# CodecB.net
KiCad netlist of a schematic drawn in Altium Designer
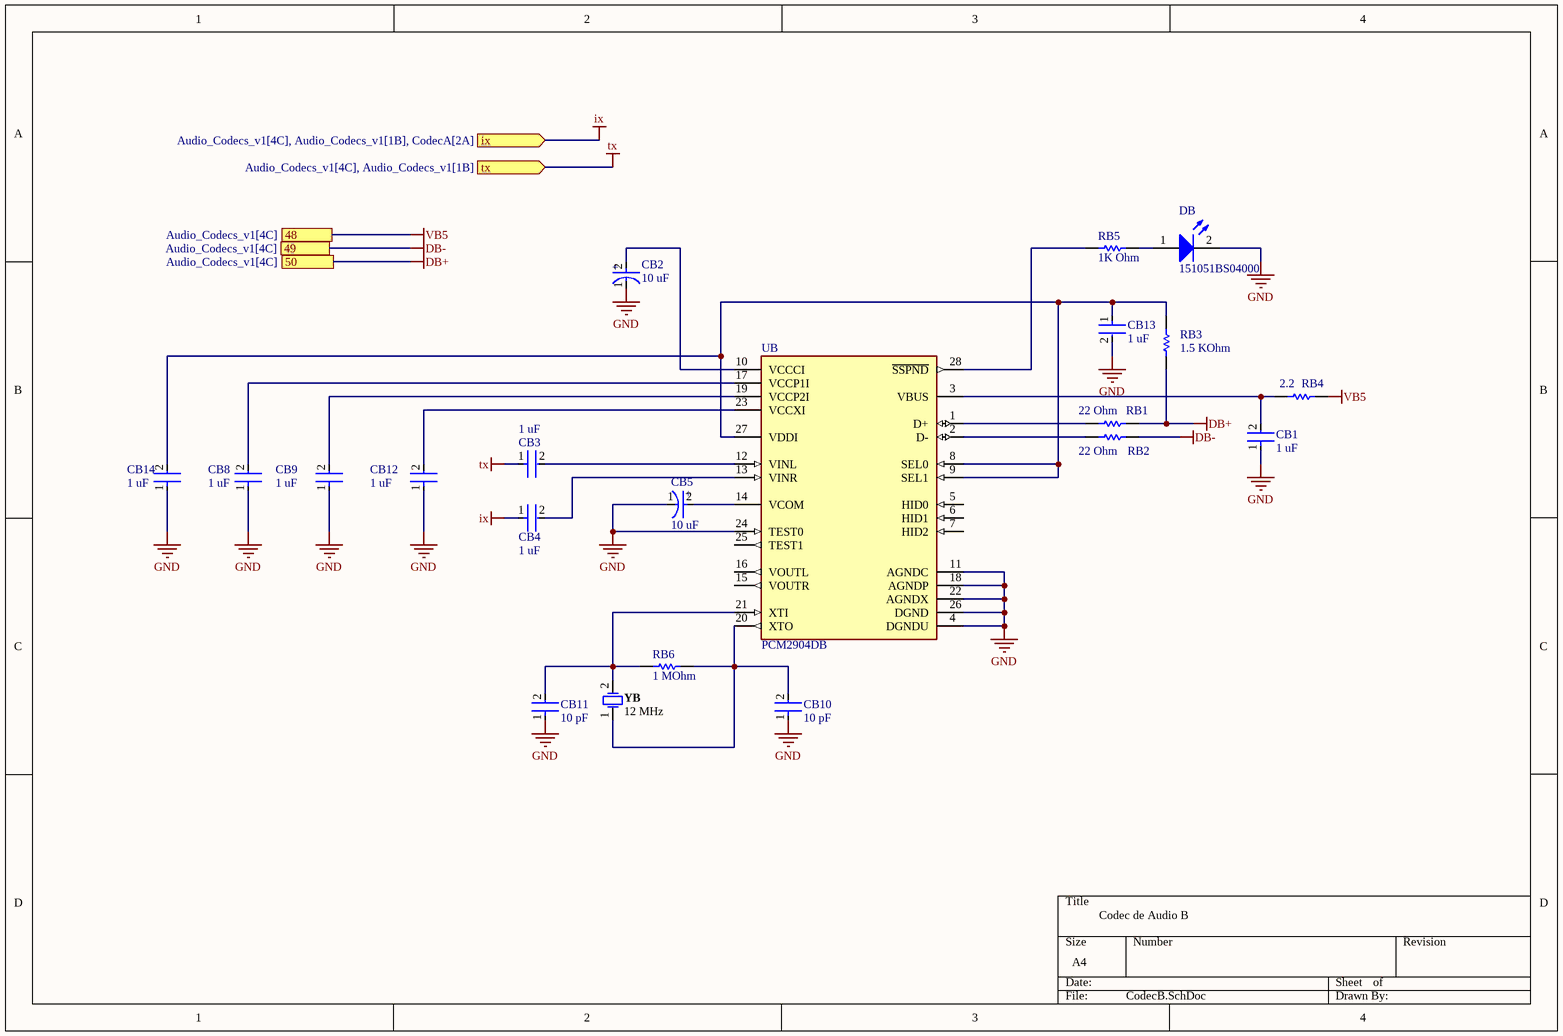
[diagram p0: CodecB.SchDoc]

(export (version "E")
  (design (tool "Eeschema 10.0.6"))
  (components
    (comp (ref "CB1")
      (value "1 uF")
      (footprint "FP-CC0805-0_85-MFG")
      (description "CAP CER 0.1UF 50V X7R 0805")
      (fields (field (name "TOLERANCE") "0.1") (field (name "MANUFACTURER PART NUMBER") "CC0805KRX7R9BB104"))
      (libsource (lib "Altium Content Vault") (part "11868f565c42a9108669ba33697ecf6"))
    )
    (comp (ref "CB2")
      (value "10 uF")
      (footprint "FP-RAD-TH-D_6_3_0_5-L_7_1-MFG")
      (description "Aluminum Electrolytic Capacitors (Radial Lead Type) 100uF ±20% 16V")
      (fields (field (name "VOLTAGE") "16V") (field (name "TOLERANCE") "20%"))
      (libsource (lib "Altium Content Vault") (part "a00bbbee19879c290e62620ae7e47b1"))
    )
    (comp (ref "CB3")
      (value "1 uF")
      (footprint "FP-CC0805-0_85-MFG")
      (description "CAP CER 0.1UF 50V X7R 0805")
      (fields (field (name "TOLERANCE") "0.1") (field (name "MANUFACTURER PART NUMBER") "CC0805KRX7R9BB104"))
      (libsource (lib "Altium Content Vault") (part "11868f565c42a9108669ba33697ecf6"))
    )
    (comp (ref "CB4")
      (value "1 uF")
      (footprint "FP-CC0805-0_85-MFG")
      (description "CAP CER 0.1UF 50V X7R 0805")
      (fields (field (name "TOLERANCE") "0.1") (field (name "MANUFACTURER PART NUMBER") "CC0805KRX7R9BB104"))
      (libsource (lib "Altium Content Vault") (part "11868f565c42a9108669ba33697ecf6"))
    )
    (comp (ref "CB5")
      (value "10 uF")
      (footprint "FP-RAD-TH-D_6_3_0_5-L_7_1-MFG")
      (description "Aluminum Electrolytic Capacitors (Radial Lead Type) 100uF ±20% 16V")
      (fields (field (name "VOLTAGE") "16V") (field (name "TOLERANCE") "20%"))
      (libsource (lib "Altium Content Vault") (part "a00bbbee19879c290e62620ae7e47b1"))
    )
    (comp (ref "CB8")
      (value "1 uF")
      (footprint "FP-CC0805-0_85-MFG")
      (description "CAP CER 0.1UF 50V X7R 0805")
      (fields (field (name "TOLERANCE") "0.1") (field (name "MANUFACTURER PART NUMBER") "CC0805KRX7R9BB104"))
      (libsource (lib "Altium Content Vault") (part "11868f565c42a9108669ba33697ecf6"))
    )
    (comp (ref "CB9")
      (value "1 uF")
      (footprint "FP-CC0805-0_85-MFG")
      (description "CAP CER 0.1UF 50V X7R 0805")
      (fields (field (name "TOLERANCE") "0.1") (field (name "MANUFACTURER PART NUMBER") "CC0805KRX7R9BB104"))
      (libsource (lib "Altium Content Vault") (part "11868f565c42a9108669ba33697ecf6"))
    )
    (comp (ref "CB10")
      (value "10 pF")
      (footprint "FP-CC0805-0_85-MFG")
      (description "CAP CER 0.1UF 50V X7R 0805")
      (fields (field (name "TOLERANCE") "0.1") (field (name "MANUFACTURER PART NUMBER") "CC0805KRX7R9BB104"))
      (libsource (lib "Altium Content Vault") (part "11868f565c42a9108669ba33697ecf6"))
    )
    (comp (ref "CB11")
      (value "10 pF")
      (footprint "FP-CC0805-0_85-MFG")
      (description "CAP CER 0.1UF 50V X7R 0805")
      (fields (field (name "TOLERANCE") "0.1") (field (name "MANUFACTURER PART NUMBER") "CC0805KRX7R9BB104"))
      (libsource (lib "Altium Content Vault") (part "11868f565c42a9108669ba33697ecf6"))
    )
    (comp (ref "CB12")
      (value "1 uF")
      (footprint "FP-CC0805-0_85-MFG")
      (description "CAP CER 0.1UF 50V X7R 0805")
      (fields (field (name "TOLERANCE") "0.1") (field (name "MANUFACTURER PART NUMBER") "CC0805KRX7R9BB104"))
      (libsource (lib "Altium Content Vault") (part "11868f565c42a9108669ba33697ecf6"))
    )
    (comp (ref "CB13")
      (value "1 uF")
      (footprint "FP-CC0805-0_85-MFG")
      (description "CAP CER 0.1UF 50V X7R 0805")
      (fields (field (name "TOLERANCE") "0.1") (field (name "MANUFACTURER PART NUMBER") "CC0805KRX7R9BB104"))
      (libsource (lib "Altium Content Vault") (part "11868f565c42a9108669ba33697ecf6"))
    )
    (comp (ref "CB14")
      (value "1 uF")
      (footprint "FP-CC0805-0_85-MFG")
      (description "CAP CER 0.1UF 50V X7R 0805")
      (fields (field (name "TOLERANCE") "0.1") (field (name "MANUFACTURER PART NUMBER") "CC0805KRX7R9BB104"))
      (libsource (lib "Altium Content Vault") (part "11868f565c42a9108669ba33697ecf6"))
    )
    (comp (ref "DB")
      (value "151051BS04000")
      (footprint "WL-TMRC_D5.9H8.7")
      (libsource (lib "Altium Content Vault") (part "LED_Blue_1A-2K"))
    )
    (comp (ref "RB1")
      (value "22 Ohm")
      (footprint "RESC2013X60X40ML20T25")
      (fields (field (name "MANUFACTURER") "Panasonic") (field (name "PART NUMBER") "ERA6AEB101V"))
      (libsource (lib "Altium Content Vault") (part "RES"))
    )
    (comp (ref "RB2")
      (value "22 Ohm")
      (footprint "RESC2013X60X40ML20T25")
      (fields (field (name "MANUFACTURER") "Panasonic") (field (name "PART NUMBER") "ERA6AEB101V"))
      (libsource (lib "Altium Content Vault") (part "RES"))
    )
    (comp (ref "RB3")
      (value "1.5 KOhm")
      (footprint "RESC2013X60X40ML20T25")
      (fields (field (name "MANUFACTURER") "Panasonic") (field (name "PART NUMBER") "ERA6AEB101V"))
      (libsource (lib "Altium Content Vault") (part "RES"))
    )
    (comp (ref "RB4")
      (value "2.2")
      (footprint "RESC2013X60X40ML20T25")
      (fields (field (name "MANUFACTURER") "Panasonic") (field (name "PART NUMBER") "ERA6AEB101V"))
      (libsource (lib "Altium Content Vault") (part "RES"))
    )
    (comp (ref "RB5")
      (value "1K Ohm")
      (footprint "RESC2013X60X40ML20T25")
      (fields (field (name "MANUFACTURER") "Panasonic") (field (name "PART NUMBER") "ERA6AEB101V"))
      (libsource (lib "Altium Content Vault") (part "RES"))
    )
    (comp (ref "RB6")
      (value "1 MOhm")
      (footprint "RESC2013X60X40ML20T25")
      (fields (field (name "MANUFACTURER") "Panasonic") (field (name "PART NUMBER") "ERA6AEB101V"))
      (libsource (lib "Altium Content Vault") (part "RES"))
    )
    (comp (ref "UB")
      (value "PCM2904DB")
      (footprint "FP-DB0028A-IPC_A")
      (description "IC STEREO AUD CODEC W/USB 28SSOP")
      (libsource (lib "Altium Content Vault") (part "e359a79613c207c48d96439f04dff7f"))
    )
    (comp (ref "YB")
      (value "12 MHz")
      (footprint "FOX-FOXSLF160-20")
      (description "Resistance Weld Thru-Hole Crystal, 16 MHz, -20 to 70 degC, 2-Pin THD, RoHS, Bulk")
      (fields (field (name "TOLERANCE") "1%"))
      (libsource (lib "Altium Content Vault") (part "XTAL-1-2-2"))
    )
  )
  (nets
    (net (code "3") (name "DB+") (class "Default")
      (node (ref "RB1") (pin "1") (pinfunction "1_1") (pintype "passive"))
      (node (ref "RB3") (pin "2") (pinfunction "2_2") (pintype "passive"))
    )
    (net (code "4") (name "DB-") (class "Default")
      (node (ref "RB2") (pin "2") (pinfunction "2_2") (pintype "passive"))
    )
    (net (code "5") (name "GND") (class "Default")
      (node (ref "CB1") (pin "1") (pinfunction "1_1") (pintype "passive"))
      (node (ref "CB10") (pin "1") (pinfunction "1_1") (pintype "passive"))
      (node (ref "CB11") (pin "1") (pinfunction "1_1") (pintype "passive"))
      (node (ref "CB12") (pin "1") (pinfunction "1_1") (pintype "passive"))
      (node (ref "CB13") (pin "2") (pinfunction "2_2") (pintype "passive"))
      (node (ref "CB14") (pin "1") (pinfunction "1_1") (pintype "passive"))
      (node (ref "CB2") (pin "1") (pinfunction "C_1") (pintype "passive"))
      (node (ref "CB5") (pin "1") (pinfunction "C_1") (pintype "passive"))
      (node (ref "CB8") (pin "1") (pinfunction "1_1") (pintype "passive"))
      (node (ref "CB9") (pin "1") (pinfunction "1_1") (pintype "passive"))
      (node (ref "DB") (pin "2") (pinfunction "K_2") (pintype "passive"))
      (node (ref "UB") (pin "11") (pinfunction "AGNDC_11") (pintype "power_in"))
      (node (ref "UB") (pin "18") (pinfunction "AGNDP_18") (pintype "power_in"))
      (node (ref "UB") (pin "22") (pinfunction "AGNDX_22") (pintype "power_in"))
      (node (ref "UB") (pin "24") (pinfunction "TEST0_24") (pintype "input"))
      (node (ref "UB") (pin "26") (pinfunction "DGND_26") (pintype "power_in"))
      (node (ref "UB") (pin "4") (pinfunction "DGNDU_4") (pintype "power_in"))
    )
    (net (code "6") (name "Net-(CB2-A)") (class "Default")
      (node (ref "CB2") (pin "2") (pinfunction "A_2") (pintype "passive"))
      (node (ref "UB") (pin "10") (pinfunction "VCCCI_10") (pintype "power_in"))
    )
    (net (code "7") (name "Net-(CB5-A)") (class "Default")
      (node (ref "CB5") (pin "2") (pinfunction "A_2") (pintype "passive"))
      (node (ref "UB") (pin "14") (pinfunction "VCOM_14") (pintype "power_in"))
    )
    (net (code "8") (name "Net-(DB-A)") (class "Default")
      (node (ref "DB") (pin "1") (pinfunction "A_1") (pintype "passive"))
      (node (ref "RB5") (pin "1") (pinfunction "1_1") (pintype "passive"))
    )
    (net (code "9") (name "Net-(UB-D+)") (class "Default")
      (node (ref "RB1") (pin "2") (pinfunction "2_2") (pintype "passive"))
      (node (ref "UB") (pin "1") (pinfunction "D+_1") (pintype "bidirectional"))
    )
    (net (code "10") (name "Net-(UB-D-)") (class "Default")
      (node (ref "RB2") (pin "1") (pinfunction "1_1") (pintype "passive"))
      (node (ref "UB") (pin "2") (pinfunction "D-_2") (pintype "bidirectional"))
    )
    (net (code "11") (name "Net-(UB-SEL0)") (class "Default")
      (node (ref "CB13") (pin "1") (pinfunction "1_1") (pintype "passive"))
      (node (ref "CB14") (pin "2") (pinfunction "2_2") (pintype "passive"))
      (node (ref "RB3") (pin "1") (pinfunction "1_1") (pintype "passive"))
      (node (ref "UB") (pin "27") (pinfunction "VDDI_27") (pintype "power_in"))
      (node (ref "UB") (pin "8") (pinfunction "SEL0_8") (pintype "input"))
      (node (ref "UB") (pin "9") (pinfunction "SEL1_9") (pintype "input"))
    )
    (net (code "12") (name "Net-(UB-VBUS)") (class "Default")
      (node (ref "CB1") (pin "2") (pinfunction "2_2") (pintype "passive"))
      (node (ref "RB4") (pin "2") (pinfunction "2_2") (pintype "passive"))
      (node (ref "UB") (pin "3") (pinfunction "VBUS_3") (pintype "power_in"))
    )
    (net (code "13") (name "Net-(UB-VCCP1I)") (class "Default")
      (node (ref "CB8") (pin "2") (pinfunction "2_2") (pintype "passive"))
      (node (ref "UB") (pin "17") (pinfunction "VCCP1I_17") (pintype "power_in"))
    )
    (net (code "14") (name "Net-(UB-VCCP2I)") (class "Default")
      (node (ref "CB9") (pin "2") (pinfunction "2_2") (pintype "passive"))
      (node (ref "UB") (pin "19") (pinfunction "VCCP2I_19") (pintype "power_in"))
    )
    (net (code "15") (name "Net-(UB-VCCXI)") (class "Default")
      (node (ref "CB12") (pin "2") (pinfunction "2_2") (pintype "passive"))
      (node (ref "UB") (pin "23") (pinfunction "VCCXI_23") (pintype "power_in"))
    )
    (net (code "16") (name "Net-(UB-VINL)") (class "Default")
      (node (ref "CB3") (pin "2") (pinfunction "2_2") (pintype "passive"))
      (node (ref "UB") (pin "12") (pinfunction "VINL_12") (pintype "input"))
    )
    (net (code "17") (name "Net-(UB-VINR)") (class "Default")
      (node (ref "CB4") (pin "2") (pinfunction "2_2") (pintype "passive"))
      (node (ref "UB") (pin "13") (pinfunction "VINR_13") (pintype "input"))
    )
    (net (code "18") (name "Net-(UB-XTI)") (class "Default")
      (node (ref "CB11") (pin "2") (pinfunction "2_2") (pintype "passive"))
      (node (ref "RB6") (pin "1") (pinfunction "1_1") (pintype "passive"))
      (node (ref "UB") (pin "21") (pinfunction "XTI_21") (pintype "input"))
      (node (ref "YB") (pin "2") (pinfunction "2_2") (pintype "passive"))
    )
    (net (code "19") (name "Net-(UB-XTO)") (class "Default")
      (node (ref "CB10") (pin "2") (pinfunction "2_2") (pintype "passive"))
      (node (ref "RB6") (pin "2") (pinfunction "2_2") (pintype "passive"))
      (node (ref "UB") (pin "20") (pinfunction "XTO_20") (pintype "output"))
      (node (ref "YB") (pin "1") (pinfunction "1_1") (pintype "passive"))
    )
    (net (code "20") (name "Net-(UB-~{SSPND})") (class "Default")
      (node (ref "RB5") (pin "2") (pinfunction "2_2") (pintype "passive"))
      (node (ref "UB") (pin "28") (pinfunction "~{SSPND}_28") (pintype "output"))
    )
    (net (code "21") (name "VB5") (class "Default")
      (node (ref "RB4") (pin "1") (pinfunction "1_1") (pintype "passive"))
    )
    (net (code "22") (name "ix") (class "Default")
      (node (ref "CB4") (pin "1") (pinfunction "1_1") (pintype "passive"))
    )
    (net (code "23") (name "tx") (class "Default")
      (node (ref "CB3") (pin "1") (pinfunction "1_1") (pintype "passive"))
    )
    (net (code "24") (name "unconnected-(UB-HID0-Pad5)") (class "Default")
      (node (ref "UB") (pin "5") (pinfunction "HID0_5") (pintype "input"))
    )
    (net (code "25") (name "unconnected-(UB-HID1-Pad6)") (class "Default")
      (node (ref "UB") (pin "6") (pinfunction "HID1_6") (pintype "input"))
    )
    (net (code "26") (name "unconnected-(UB-HID2-Pad7)") (class "Default")
      (node (ref "UB") (pin "7") (pinfunction "HID2_7") (pintype "input"))
    )
    (net (code "27") (name "unconnected-(UB-TEST1-Pad25)") (class "Default")
      (node (ref "UB") (pin "25") (pinfunction "TEST1_25") (pintype "output"))
    )
    (net (code "28") (name "unconnected-(UB-VOUTL-Pad16)") (class "Default")
      (node (ref "UB") (pin "16") (pinfunction "VOUTL_16") (pintype "output"))
    )
    (net (code "29") (name "unconnected-(UB-VOUTR-Pad15)") (class "Default")
      (node (ref "UB") (pin "15") (pinfunction "VOUTR_15") (pintype "output"))
    )
  )
)
